# rgb-wifi.net
KiCad netlist of a schematic drawn in EAGLE
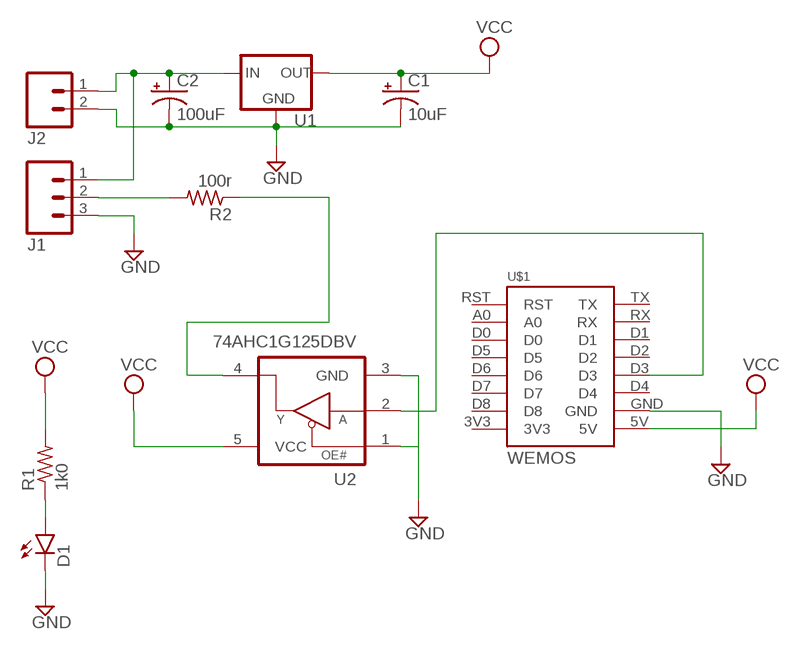
[diagram p0: schematic, sheet 1]

(export (version "E")
  (design (tool "Eeschema 10.0.6"))
  (components
    (comp (ref "C1")
      (value "10uF")
      (footprint "eagle-import:CPOL-RADIAL-10UF-25V")
      (libsource (lib "eagle-import") (part "10UF-25V-20%(PTH)"))
    )
    (comp (ref "C2")
      (value "100uF")
      (footprint "eagle-import:CPOL-RADIAL-100UF-25V")
      (libsource (lib "eagle-import") (part "100UF-25V-20%(PTH)"))
    )
    (comp (ref "D1")
      (value "LED3MM")
      (footprint "eagle-import:LED3MM")
      (libsource (lib "eagle-import") (part "LED3MM"))
    )
    (comp (ref "J1")
      (value "M03SCREW")
      (footprint "eagle-import:SCREWTERMINAL-3.5MM-3")
      (libsource (lib "eagle-import") (part "M03SCREW"))
    )
    (comp (ref "J2")
      (value "M023.5MM")
      (footprint "eagle-import:SCREWTERMINAL-3.5MM-2")
      (libsource (lib "eagle-import") (part "M023.5MM"))
    )
    (comp (ref "R1")
      (value "1k0")
      (footprint "eagle-import:0204V")
      (libsource (lib "eagle-import") (part "R-US_0204/2V"))
    )
    (comp (ref "R2")
      (value "100r")
      (footprint "eagle-import:0204V")
      (libsource (lib "eagle-import") (part "R-US_0204/2V"))
    )
    (comp (ref "U$1")
      (value "WEMOS")
      (footprint "eagle-import:WEMOS")
      (libsource (lib "eagle-import") (part "WEMOS"))
    )
    (comp (ref "U1")
      (value "+12v")
      (footprint "eagle-import:TO-252")
      (libsource (lib "eagle-import") (part "V_REG_78XX7812"))
    )
    (comp (ref "U2")
      (value "74AHC1G125DBV")
      (footprint "eagle-import:SOT23-5")
      (libsource (lib "eagle-import") (part "74AHC1G125DBV"))
    )
  )
  (nets
    (net (code "1") (name "GND") (class "Default")
      (node (ref "C1") (pin "2") (pinfunction "-_2") (pintype "passive"))
      (node (ref "C2") (pin "2") (pinfunction "-_2") (pintype "passive"))
      (node (ref "D1") (pin "K") (pinfunction "C_K") (pintype "passive"))
      (node (ref "J1") (pin "3") (pinfunction "3_3") (pintype "passive"))
      (node (ref "J2") (pin "2") (pinfunction "2_2") (pintype "passive"))
      (node (ref "U$1") (pin "GND") (pinfunction "GND_GND") (pintype "bidirectional"))
      (node (ref "U1") (pin "3") (pinfunction "GND_3") (pintype "input"))
      (node (ref "U2") (pin "1") (pinfunction "OE#_1") (pintype "input"))
      (node (ref "U2") (pin "3") (pinfunction "GND_3") (pintype "power_in"))
    )
    (net (code "2") (name "Net-(C2-+)") (class "Default")
      (node (ref "C2") (pin "1") (pinfunction "+_1") (pintype "passive"))
      (node (ref "J1") (pin "1") (pinfunction "1_1") (pintype "passive"))
      (node (ref "J2") (pin "1") (pinfunction "1_1") (pintype "passive"))
      (node (ref "U1") (pin "1") (pinfunction "IN_1") (pintype "input"))
    )
    (net (code "3") (name "Net-(D1-PadA)") (class "Default")
      (node (ref "D1") (pin "A") (pinfunction "A_A") (pintype "passive"))
      (node (ref "R1") (pin "1") (pinfunction "1_1") (pintype "passive"))
    )
    (net (code "4") (name "Net-(J1-Pad2)") (class "Default")
      (node (ref "J1") (pin "2") (pinfunction "2_2") (pintype "passive"))
      (node (ref "R2") (pin "2") (pinfunction "2_2") (pintype "passive"))
    )
    (net (code "5") (name "Net-(U2-A)") (class "Default")
      (node (ref "U$1") (pin "D3") (pinfunction "D3_D3") (pintype "bidirectional"))
      (node (ref "U2") (pin "2") (pinfunction "A_2") (pintype "input"))
    )
    (net (code "6") (name "Net-(U2-Y)") (class "Default")
      (node (ref "R2") (pin "1") (pinfunction "1_1") (pintype "passive"))
      (node (ref "U2") (pin "4") (pinfunction "Y_4") (pintype "output"))
    )
    (net (code "7") (name "VCC") (class "Default")
      (node (ref "C1") (pin "1") (pinfunction "+_1") (pintype "passive"))
      (node (ref "R1") (pin "2") (pinfunction "2_2") (pintype "passive"))
      (node (ref "U$1") (pin "5V") (pinfunction "5V_5V") (pintype "bidirectional"))
      (node (ref "U1") (pin "2") (pinfunction "OUT_2") (pintype "passive"))
      (node (ref "U2") (pin "5") (pinfunction "VCC_5") (pintype "power_in"))
    )
    (net (code "8") (name "unconnected-(U$1-Pad3V3)") (class "Default")
      (node (ref "U$1") (pin "3V3") (pinfunction "3V3_3V3") (pintype "bidirectional"))
    )
    (net (code "9") (name "unconnected-(U$1-PadA0)") (class "Default")
      (node (ref "U$1") (pin "A0") (pinfunction "A0_A0") (pintype "bidirectional"))
    )
    (net (code "10") (name "unconnected-(U$1-PadD0)") (class "Default")
      (node (ref "U$1") (pin "D0") (pinfunction "D0_D0") (pintype "bidirectional"))
    )
    (net (code "11") (name "unconnected-(U$1-PadD1)") (class "Default")
      (node (ref "U$1") (pin "D1") (pinfunction "D1_D1") (pintype "bidirectional"))
    )
    (net (code "12") (name "unconnected-(U$1-PadD2)") (class "Default")
      (node (ref "U$1") (pin "D2") (pinfunction "D2_D2") (pintype "bidirectional"))
    )
    (net (code "13") (name "unconnected-(U$1-PadD4)") (class "Default")
      (node (ref "U$1") (pin "D4") (pinfunction "D4_D4") (pintype "bidirectional"))
    )
    (net (code "14") (name "unconnected-(U$1-PadD5)") (class "Default")
      (node (ref "U$1") (pin "D5") (pinfunction "D5_D5") (pintype "bidirectional"))
    )
    (net (code "15") (name "unconnected-(U$1-PadD6)") (class "Default")
      (node (ref "U$1") (pin "D6") (pinfunction "D6_D6") (pintype "bidirectional"))
    )
    (net (code "16") (name "unconnected-(U$1-PadD7)") (class "Default")
      (node (ref "U$1") (pin "D7") (pinfunction "D7_D7") (pintype "bidirectional"))
    )
    (net (code "17") (name "unconnected-(U$1-PadD8)") (class "Default")
      (node (ref "U$1") (pin "D8") (pinfunction "D8_D8") (pintype "bidirectional"))
    )
    (net (code "18") (name "unconnected-(U$1-PadRST)") (class "Default")
      (node (ref "U$1") (pin "RST") (pinfunction "RST_RST") (pintype "bidirectional"))
    )
    (net (code "19") (name "unconnected-(U$1-PadRX)") (class "Default")
      (node (ref "U$1") (pin "RX") (pinfunction "RX_RX") (pintype "bidirectional"))
    )
    (net (code "20") (name "unconnected-(U$1-PadTX)") (class "Default")
      (node (ref "U$1") (pin "TX") (pinfunction "TX_TX") (pintype "bidirectional"))
    )
  )
)
